# ShieldPotencia.net
KiCad netlist of a schematic drawn in EAGLE
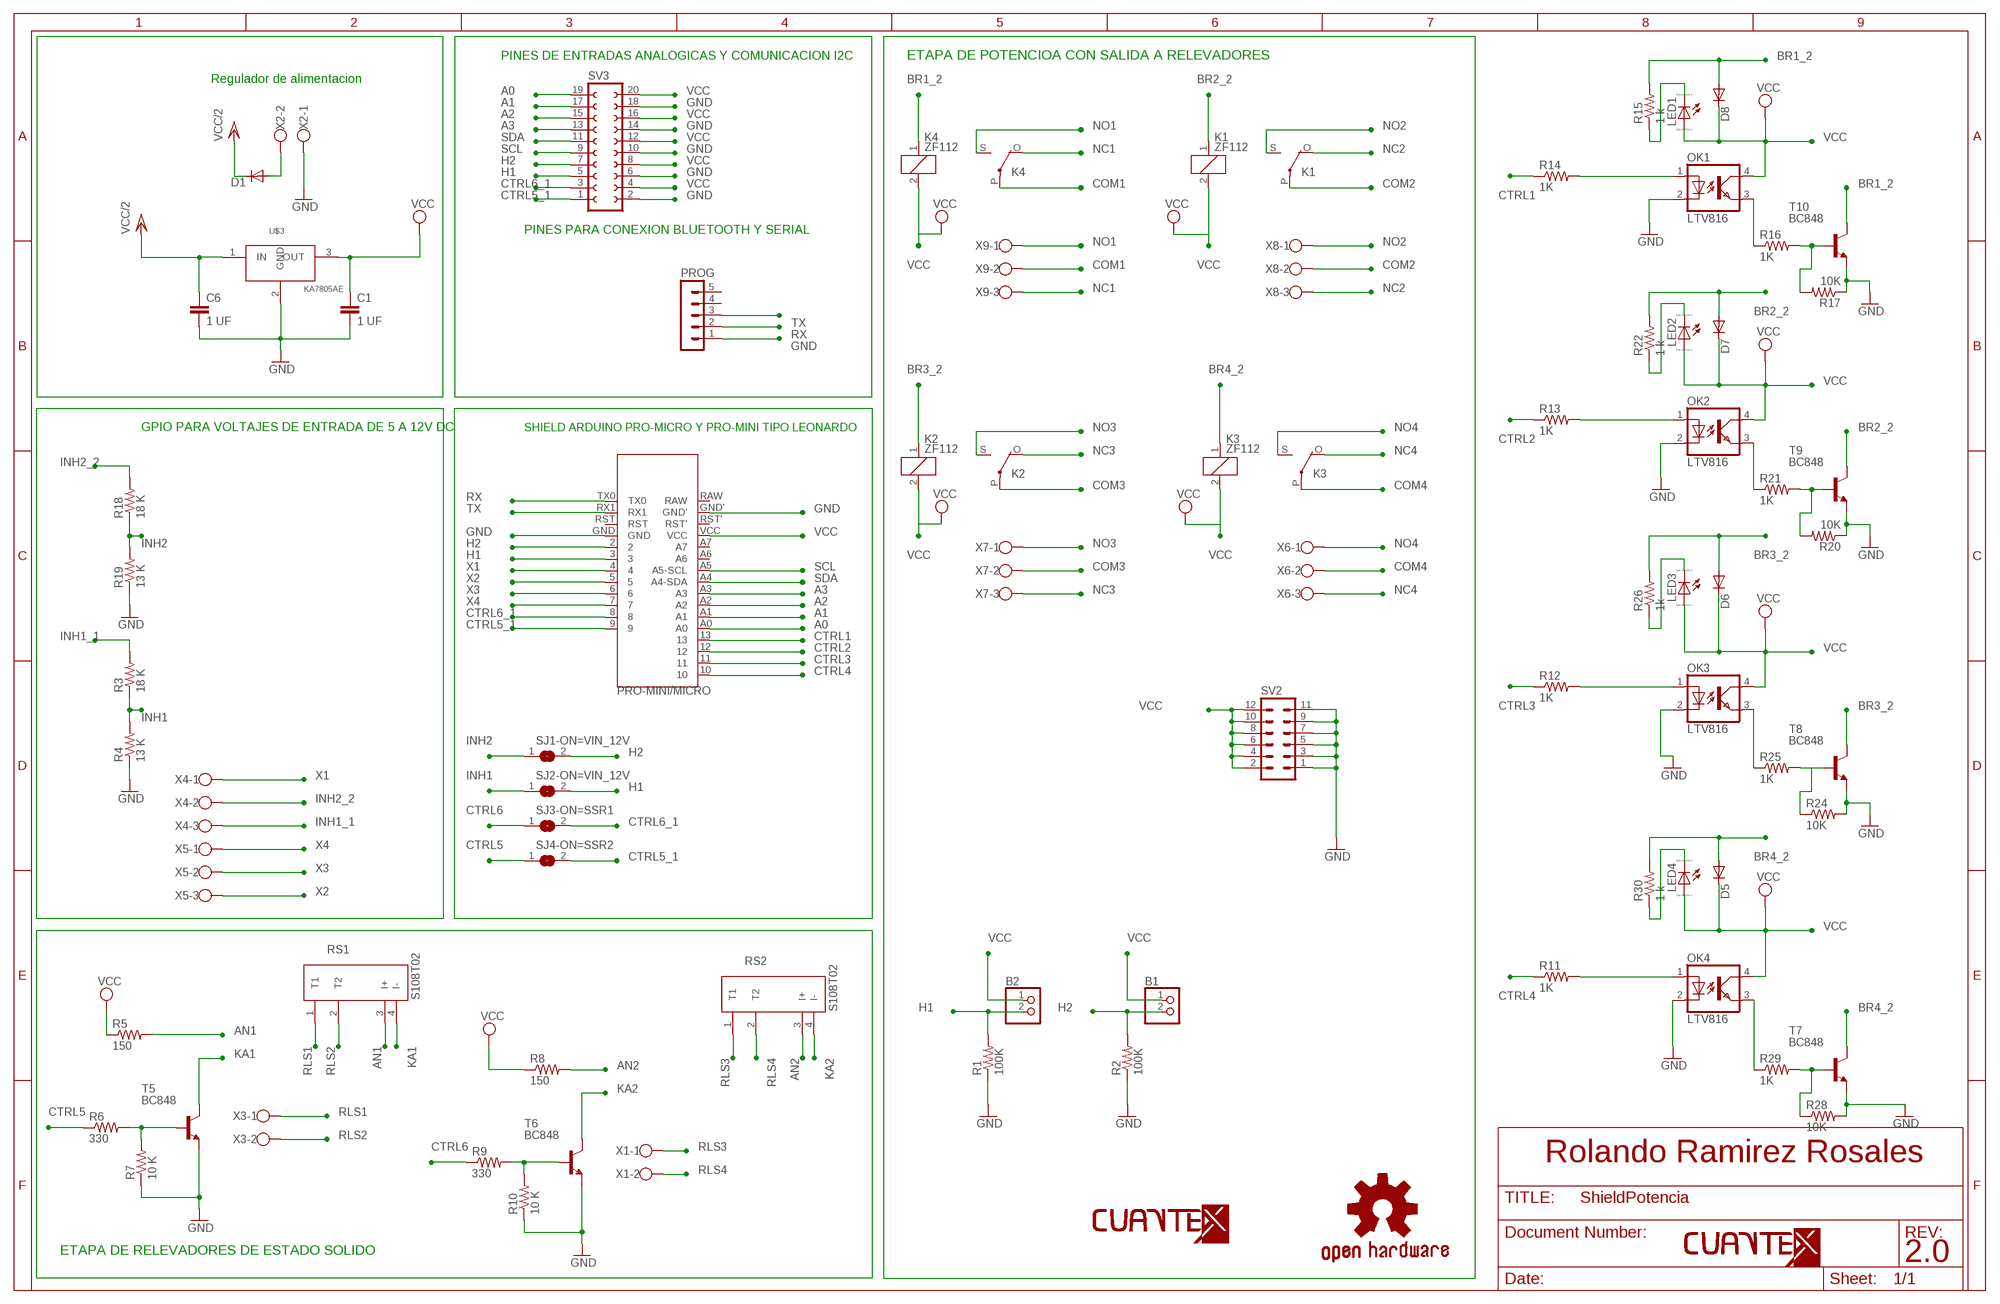
[diagram p0: schematic, sheet 1]

(export (version "E")
  (design (tool "Eeschema 10.0.6"))
  (components
    (comp (ref "B1")
      (value "PINHD-1X2")
      (footprint "eagle-import:1X02")
      (libsource (lib "eagle-import") (part "PINHD-1X2"))
    )
    (comp (ref "B2")
      (value "PINHD-1X2")
      (footprint "eagle-import:1X02")
      (libsource (lib "eagle-import") (part "PINHD-1X2"))
    )
    (comp (ref "C1")
      (value "1 UF")
      (footprint "eagle-import:C0603")
      (libsource (lib "eagle-import") (part "C-EUC0603"))
    )
    (comp (ref "C6")
      (value "1 UF")
      (footprint "eagle-import:C0603")
      (libsource (lib "eagle-import") (part "C-EUC0603"))
    )
    (comp (ref "D1")
      (value "DIODE-SMB")
      (footprint "eagle-import:SMB")
      (libsource (lib "eagle-import") (part "DIODE-SMB"))
    )
    (comp (ref "D5")
      (value "DIODE-SMB")
      (footprint "eagle-import:SMB")
      (libsource (lib "eagle-import") (part "DIODE-SMB"))
    )
    (comp (ref "D6")
      (value "DIODE-SMB")
      (footprint "eagle-import:SMB")
      (libsource (lib "eagle-import") (part "DIODE-SMB"))
    )
    (comp (ref "D7")
      (value "DIODE-SMB")
      (footprint "eagle-import:SMB")
      (libsource (lib "eagle-import") (part "DIODE-SMB"))
    )
    (comp (ref "D8")
      (value "DIODE-SMB")
      (footprint "eagle-import:SMB")
      (libsource (lib "eagle-import") (part "DIODE-SMB"))
    )
    (comp (ref "GOLD_ORB_SM1")
      (value "OSHWLOGO_GOLD_ORB_SM")
      (footprint "eagle-import:OSHW2")
      (libsource (lib "eagle-import") (part "OSHWLOGO_GOLD_ORB_SM"))
    )
    (comp (ref "K1")
      (value "ZF112")
      (footprint "eagle-import:ZF112")
      (libsource (lib "eagle-import") (part "ZF112"))
    )
    (comp (ref "K2")
      (value "ZF112")
      (footprint "eagle-import:ZF112")
      (libsource (lib "eagle-import") (part "ZF112"))
    )
    (comp (ref "K3")
      (value "ZF112")
      (footprint "eagle-import:ZF112")
      (libsource (lib "eagle-import") (part "ZF112"))
    )
    (comp (ref "K4")
      (value "ZF112")
      (footprint "eagle-import:ZF112")
      (libsource (lib "eagle-import") (part "ZF112"))
    )
    (comp (ref "LED1")
      (value "LED_ESML0603")
      (footprint "eagle-import:LED_SML0603")
      (libsource (lib "eagle-import") (part "LED_ESML0603"))
    )
    (comp (ref "LED2")
      (value "LED_ESML0603")
      (footprint "eagle-import:LED_SML0603")
      (libsource (lib "eagle-import") (part "LED_ESML0603"))
    )
    (comp (ref "LED3")
      (value "LED_ESML0603")
      (footprint "eagle-import:LED_SML0603")
      (libsource (lib "eagle-import") (part "LED_ESML0603"))
    )
    (comp (ref "LED4")
      (value "LED_ESML0603")
      (footprint "eagle-import:LED_SML0603")
      (libsource (lib "eagle-import") (part "LED_ESML0603"))
    )
    (comp (ref "OK1")
      (value "LTV816")
      (footprint "eagle-import:DIL04")
      (libsource (lib "eagle-import") (part "LTV816"))
    )
    (comp (ref "OK2")
      (value "LTV816")
      (footprint "eagle-import:DIL04")
      (libsource (lib "eagle-import") (part "LTV816"))
    )
    (comp (ref "OK3")
      (value "LTV816")
      (footprint "eagle-import:DIL04")
      (libsource (lib "eagle-import") (part "LTV816"))
    )
    (comp (ref "OK4")
      (value "LTV816")
      (footprint "eagle-import:DIL04")
      (libsource (lib "eagle-import") (part "LTV816"))
    )
    (comp (ref "PRO-MINI/MICRO")
      (value "ARDUINO_PRO_MINI_V1")
      (footprint "eagle-import:ARDUINO_PRO_MINI_V1")
      (libsource (lib "eagle-import") (part "ARDUINO_PRO_MINI_V1"))
    )
    (comp (ref "PROG")
      (value "MA05-1")
      (footprint "eagle-import:MA05-1")
      (libsource (lib "eagle-import") (part "MA05-1"))
    )
    (comp (ref "R1")
      (value "100K")
      (footprint "eagle-import:R0603")
      (libsource (lib "eagle-import") (part "R-US_R0603"))
    )
    (comp (ref "R2")
      (value "100K")
      (footprint "eagle-import:R0603")
      (libsource (lib "eagle-import") (part "R-US_R0603"))
    )
    (comp (ref "R3")
      (value "18 K")
      (footprint "eagle-import:R1206")
      (libsource (lib "eagle-import") (part "R-US_R1206"))
    )
    (comp (ref "R4")
      (value "13 K")
      (footprint "eagle-import:R1206")
      (libsource (lib "eagle-import") (part "R-US_R1206"))
    )
    (comp (ref "R5")
      (value "150")
      (footprint "eagle-import:R0603")
      (libsource (lib "eagle-import") (part "R-US_R0603"))
    )
    (comp (ref "R6")
      (value "330")
      (footprint "eagle-import:R0603")
      (libsource (lib "eagle-import") (part "R-US_R0603"))
    )
    (comp (ref "R7")
      (value "10 K")
      (footprint "eagle-import:R0603")
      (libsource (lib "eagle-import") (part "R-US_R0603"))
    )
    (comp (ref "R8")
      (value "150")
      (footprint "eagle-import:R0603")
      (libsource (lib "eagle-import") (part "R-US_R0603"))
    )
    (comp (ref "R9")
      (value "330")
      (footprint "eagle-import:R0603")
      (libsource (lib "eagle-import") (part "R-US_R0603"))
    )
    (comp (ref "R10")
      (value "10 K")
      (footprint "eagle-import:R0603")
      (libsource (lib "eagle-import") (part "R-US_R0603"))
    )
    (comp (ref "R11")
      (value "1K")
      (footprint "eagle-import:R0603")
      (libsource (lib "eagle-import") (part "R-US_R0603"))
    )
    (comp (ref "R12")
      (value "1K")
      (footprint "eagle-import:R0603")
      (libsource (lib "eagle-import") (part "R-US_R0603"))
    )
    (comp (ref "R13")
      (value "1K")
      (footprint "eagle-import:R0603")
      (libsource (lib "eagle-import") (part "R-US_R0603"))
    )
    (comp (ref "R14")
      (value "1K")
      (footprint "eagle-import:R0603")
      (libsource (lib "eagle-import") (part "R-US_R0603"))
    )
    (comp (ref "R15")
      (value "1 k")
      (footprint "eagle-import:R0603")
      (libsource (lib "eagle-import") (part "R-US_R0603"))
    )
    (comp (ref "R16")
      (value "1K")
      (footprint "eagle-import:R0603")
      (libsource (lib "eagle-import") (part "R-US_R0603"))
    )
    (comp (ref "R17")
      (value "10K")
      (footprint "eagle-import:R0603")
      (libsource (lib "eagle-import") (part "R-US_R0603"))
    )
    (comp (ref "R18")
      (value "18 K")
      (footprint "eagle-import:R1206")
      (libsource (lib "eagle-import") (part "R-US_R1206"))
    )
    (comp (ref "R19")
      (value "13 K")
      (footprint "eagle-import:R1206")
      (libsource (lib "eagle-import") (part "R-US_R1206"))
    )
    (comp (ref "R20")
      (value "10K")
      (footprint "eagle-import:R0603")
      (libsource (lib "eagle-import") (part "R-US_R0603"))
    )
    (comp (ref "R21")
      (value "1K")
      (footprint "eagle-import:R0603")
      (libsource (lib "eagle-import") (part "R-US_R0603"))
    )
    (comp (ref "R22")
      (value "1 k")
      (footprint "eagle-import:R0603")
      (libsource (lib "eagle-import") (part "R-US_R0603"))
    )
    (comp (ref "R24")
      (value "10K")
      (footprint "eagle-import:R0603")
      (libsource (lib "eagle-import") (part "R-US_R0603"))
    )
    (comp (ref "R25")
      (value "1K")
      (footprint "eagle-import:R0603")
      (libsource (lib "eagle-import") (part "R-US_R0603"))
    )
    (comp (ref "R26")
      (value "1k")
      (footprint "eagle-import:R0603")
      (libsource (lib "eagle-import") (part "R-US_R0603"))
    )
    (comp (ref "R28")
      (value "10K")
      (footprint "eagle-import:R0603")
      (libsource (lib "eagle-import") (part "R-US_R0603"))
    )
    (comp (ref "R29")
      (value "1K")
      (footprint "eagle-import:R0603")
      (libsource (lib "eagle-import") (part "R-US_R0603"))
    )
    (comp (ref "R30")
      (value "1 k")
      (footprint "eagle-import:R0603")
      (libsource (lib "eagle-import") (part "R-US_R0603"))
    )
    (comp (ref "RS1")
      (value "S108T02")
      (footprint "eagle-import:SIP4PIN")
      (libsource (lib "eagle-import") (part "S108T02"))
    )
    (comp (ref "RS2")
      (value "S108T02")
      (footprint "eagle-import:SIP4PIN")
      (libsource (lib "eagle-import") (part "S108T02"))
    )
    (comp (ref "SJ1-ON=VIN_12V")
      (value "SJ")
      (footprint "eagle-import:SJ")
      (libsource (lib "eagle-import") (part "SJ"))
    )
    (comp (ref "SJ2-ON=VIN_12V")
      (value "SJ")
      (footprint "eagle-import:SJ")
      (libsource (lib "eagle-import") (part "SJ"))
    )
    (comp (ref "SJ3-ON=SSR1")
      (value "SJ")
      (footprint "eagle-import:SJ")
      (libsource (lib "eagle-import") (part "SJ"))
    )
    (comp (ref "SJ4-ON=SSR2")
      (value "SJ")
      (footprint "eagle-import:SJ")
      (libsource (lib "eagle-import") (part "SJ"))
    )
    (comp (ref "SV2")
      (value "MA06-2")
      (footprint "eagle-import:MA06-2")
      (libsource (lib "eagle-import") (part "MA06-2"))
    )
    (comp (ref "SV3")
      (value "FE10-2")
      (footprint "eagle-import:FE10-2")
      (libsource (lib "eagle-import") (part "FE10-2"))
    )
    (comp (ref "T5")
      (value "BC848")
      (footprint "eagle-import:SOT23")
      (libsource (lib "eagle-import") (part "BC848"))
    )
    (comp (ref "T6")
      (value "BC848")
      (footprint "eagle-import:SOT23")
      (libsource (lib "eagle-import") (part "BC848"))
    )
    (comp (ref "T7")
      (value "BC848")
      (footprint "eagle-import:SOT23")
      (libsource (lib "eagle-import") (part "BC848"))
    )
    (comp (ref "T8")
      (value "BC848")
      (footprint "eagle-import:SOT23")
      (libsource (lib "eagle-import") (part "BC848"))
    )
    (comp (ref "T9")
      (value "BC848")
      (footprint "eagle-import:SOT23")
      (libsource (lib "eagle-import") (part "BC848"))
    )
    (comp (ref "T10")
      (value "BC848")
      (footprint "eagle-import:SOT23")
      (libsource (lib "eagle-import") (part "BC848"))
    )
    (comp (ref "U$1")
      (value "LOGO-TOP-50MM")
      (footprint "eagle-import:C-3")
      (libsource (lib "eagle-import") (part "LOGO-TOP-50MM"))
    )
    (comp (ref "U$2")
      (value "LOGO-TOP-20MM")
      (footprint "eagle-import:C-0")
      (libsource (lib "eagle-import") (part "LOGO-TOP-20MM"))
    )
    (comp (ref "U$3")
      (value "KA7805AE")
      (footprint "eagle-import:DPAK")
      (libsource (lib "eagle-import") (part "KA7805AE"))
    )
    (comp (ref "X1")
      (value "W237-102")
      (footprint "eagle-import:W237-102")
      (fields (field (name "MPN") "237-102"))
      (libsource (lib "eagle-import") (part "W237-102"))
    )
    (comp (ref "X2")
      (value "W237-102")
      (footprint "eagle-import:W237-102")
      (fields (field (name "MPN") "237-102"))
      (libsource (lib "eagle-import") (part "W237-102"))
    )
    (comp (ref "X3")
      (value "W237-102")
      (footprint "eagle-import:W237-102")
      (fields (field (name "MPN") "237-102"))
      (libsource (lib "eagle-import") (part "W237-102"))
    )
    (comp (ref "X4")
      (value "W237-103")
      (footprint "eagle-import:W237-103")
      (fields (field (name "MPN") "237-103"))
      (libsource (lib "eagle-import") (part "W237-103"))
    )
    (comp (ref "X5")
      (value "W237-103")
      (footprint "eagle-import:W237-103")
      (fields (field (name "MPN") "237-103"))
      (libsource (lib "eagle-import") (part "W237-103"))
    )
    (comp (ref "X6")
      (value "W237-103")
      (footprint "eagle-import:W237-103")
      (fields (field (name "MPN") "237-103"))
      (libsource (lib "eagle-import") (part "W237-103"))
    )
    (comp (ref "X7")
      (value "W237-103")
      (footprint "eagle-import:W237-103")
      (fields (field (name "MPN") "237-103"))
      (libsource (lib "eagle-import") (part "W237-103"))
    )
    (comp (ref "X8")
      (value "W237-103")
      (footprint "eagle-import:W237-103")
      (fields (field (name "MPN") "237-103"))
      (libsource (lib "eagle-import") (part "W237-103"))
    )
    (comp (ref "X9")
      (value "W237-103")
      (footprint "eagle-import:W237-103")
      (fields (field (name "MPN") "237-103"))
      (libsource (lib "eagle-import") (part "W237-103"))
    )
  )
  (nets
    (net (code "1") (name "/A0") (class "Default")
      (node (ref "PRO-MINI/MICRO") (pin "A0") (pinfunction "A0_A0") (pintype "bidirectional"))
      (node (ref "SV3") (pin "19") (pinfunction "19_19") (pintype "passive"))
    )
    (net (code "2") (name "/A1") (class "Default")
      (node (ref "PRO-MINI/MICRO") (pin "A1") (pinfunction "A1_A1") (pintype "bidirectional"))
      (node (ref "SV3") (pin "17") (pinfunction "17_17") (pintype "passive"))
    )
    (net (code "3") (name "/A2") (class "Default")
      (node (ref "PRO-MINI/MICRO") (pin "A2") (pinfunction "A2_A2") (pintype "bidirectional"))
      (node (ref "SV3") (pin "15") (pinfunction "15_15") (pintype "passive"))
    )
    (net (code "4") (name "/A3") (class "Default")
      (node (ref "PRO-MINI/MICRO") (pin "A3") (pinfunction "A3_A3") (pintype "bidirectional"))
      (node (ref "SV3") (pin "13") (pinfunction "13_13") (pintype "passive"))
    )
    (net (code "5") (name "/AN1") (class "Default")
      (node (ref "R5") (pin "2") (pinfunction "2_2") (pintype "passive"))
      (node (ref "RS1") (pin "3") (pinfunction "I+_3") (pintype "bidirectional"))
    )
    (net (code "6") (name "/AN2") (class "Default")
      (node (ref "R8") (pin "2") (pinfunction "2_2") (pintype "passive"))
      (node (ref "RS2") (pin "3") (pinfunction "I+_3") (pintype "bidirectional"))
    )
    (net (code "7") (name "/BR1_2") (class "Default")
      (node (ref "D8") (pin "A") (pinfunction "A_A") (pintype "passive"))
      (node (ref "K4") (pin "1") (pinfunction "1_1") (pintype "passive"))
      (node (ref "R15") (pin "2") (pinfunction "2_2") (pintype "passive"))
      (node (ref "T10") (pin "3") (pinfunction "C_3") (pintype "passive"))
    )
    (net (code "8") (name "/BR2_2") (class "Default")
      (node (ref "D7") (pin "A") (pinfunction "A_A") (pintype "passive"))
      (node (ref "K1") (pin "1") (pinfunction "1_1") (pintype "passive"))
      (node (ref "R22") (pin "2") (pinfunction "2_2") (pintype "passive"))
      (node (ref "T9") (pin "3") (pinfunction "C_3") (pintype "passive"))
    )
    (net (code "9") (name "/BR3_2") (class "Default")
      (node (ref "D6") (pin "A") (pinfunction "A_A") (pintype "passive"))
      (node (ref "K2") (pin "1") (pinfunction "1_1") (pintype "passive"))
      (node (ref "R26") (pin "2") (pinfunction "2_2") (pintype "passive"))
      (node (ref "T8") (pin "3") (pinfunction "C_3") (pintype "passive"))
    )
    (net (code "10") (name "/BR4_2") (class "Default")
      (node (ref "D5") (pin "A") (pinfunction "A_A") (pintype "passive"))
      (node (ref "K3") (pin "1") (pinfunction "1_1") (pintype "passive"))
      (node (ref "R30") (pin "2") (pinfunction "2_2") (pintype "passive"))
      (node (ref "T7") (pin "3") (pinfunction "C_3") (pintype "passive"))
    )
    (net (code "11") (name "/COM1") (class "Default")
      (node (ref "K4") (pin "P") (pinfunction "P_P") (pintype "passive"))
      (node (ref "X9") (pin "2") (pinfunction "KL_2") (pintype "passive"))
    )
    (net (code "12") (name "/COM2") (class "Default")
      (node (ref "K1") (pin "P") (pinfunction "P_P") (pintype "passive"))
      (node (ref "X8") (pin "2") (pinfunction "KL_2") (pintype "passive"))
    )
    (net (code "13") (name "/COM3") (class "Default")
      (node (ref "K2") (pin "P") (pinfunction "P_P") (pintype "passive"))
      (node (ref "X7") (pin "2") (pinfunction "KL_2") (pintype "passive"))
    )
    (net (code "14") (name "/COM4") (class "Default")
      (node (ref "K3") (pin "P") (pinfunction "P_P") (pintype "passive"))
      (node (ref "X6") (pin "2") (pinfunction "KL_2") (pintype "passive"))
    )
    (net (code "15") (name "/CTRL1") (class "Default")
      (node (ref "PRO-MINI/MICRO") (pin "13") (pinfunction "13_13") (pintype "bidirectional"))
      (node (ref "R14") (pin "1") (pinfunction "1_1") (pintype "passive"))
    )
    (net (code "16") (name "/CTRL2") (class "Default")
      (node (ref "PRO-MINI/MICRO") (pin "12") (pinfunction "12_12") (pintype "bidirectional"))
      (node (ref "R13") (pin "1") (pinfunction "1_1") (pintype "passive"))
    )
    (net (code "17") (name "/CTRL3") (class "Default")
      (node (ref "PRO-MINI/MICRO") (pin "11") (pinfunction "11_11") (pintype "bidirectional"))
      (node (ref "R12") (pin "1") (pinfunction "1_1") (pintype "passive"))
    )
    (net (code "18") (name "/CTRL4") (class "Default")
      (node (ref "PRO-MINI/MICRO") (pin "10") (pinfunction "10_10") (pintype "bidirectional"))
      (node (ref "R11") (pin "1") (pinfunction "1_1") (pintype "passive"))
    )
    (net (code "19") (name "/CTRL5") (class "Default")
      (node (ref "R6") (pin "1") (pinfunction "1_1") (pintype "passive"))
      (node (ref "SJ4-ON=SSR2") (pin "1") (pinfunction "1_1") (pintype "passive"))
    )
    (net (code "20") (name "/CTRL5_1") (class "Default")
      (node (ref "PRO-MINI/MICRO") (pin "9") (pinfunction "9_9") (pintype "bidirectional"))
      (node (ref "SJ4-ON=SSR2") (pin "2") (pinfunction "2_2") (pintype "passive"))
      (node (ref "SV3") (pin "1") (pinfunction "1_1") (pintype "passive"))
    )
    (net (code "21") (name "/CTRL6") (class "Default")
      (node (ref "R9") (pin "1") (pinfunction "1_1") (pintype "passive"))
      (node (ref "SJ3-ON=SSR1") (pin "1") (pinfunction "1_1") (pintype "passive"))
    )
    (net (code "22") (name "/CTRL6_1") (class "Default")
      (node (ref "PRO-MINI/MICRO") (pin "8") (pinfunction "8_8") (pintype "bidirectional"))
      (node (ref "SJ3-ON=SSR1") (pin "2") (pinfunction "2_2") (pintype "passive"))
      (node (ref "SV3") (pin "3") (pinfunction "3_3") (pintype "passive"))
    )
    (net (code "23") (name "/H1") (class "Default")
      (node (ref "B2") (pin "2") (pinfunction "2_2") (pintype "passive"))
      (node (ref "PRO-MINI/MICRO") (pin "3") (pinfunction "3_3") (pintype "bidirectional"))
      (node (ref "R1") (pin "2") (pinfunction "2_2") (pintype "passive"))
      (node (ref "SJ2-ON=VIN_12V") (pin "2") (pinfunction "2_2") (pintype "passive"))
      (node (ref "SV3") (pin "5") (pinfunction "5_5") (pintype "passive"))
    )
    (net (code "24") (name "/H2") (class "Default")
      (node (ref "B1") (pin "2") (pinfunction "2_2") (pintype "passive"))
      (node (ref "PRO-MINI/MICRO") (pin "2") (pinfunction "2_2") (pintype "bidirectional"))
      (node (ref "R2") (pin "2") (pinfunction "2_2") (pintype "passive"))
      (node (ref "SJ1-ON=VIN_12V") (pin "2") (pinfunction "2_2") (pintype "passive"))
      (node (ref "SV3") (pin "7") (pinfunction "7_7") (pintype "passive"))
    )
    (net (code "25") (name "/INH1") (class "Default")
      (node (ref "R3") (pin "1") (pinfunction "1_1") (pintype "passive"))
      (node (ref "R4") (pin "2") (pinfunction "2_2") (pintype "passive"))
      (node (ref "SJ2-ON=VIN_12V") (pin "1") (pinfunction "1_1") (pintype "passive"))
    )
    (net (code "26") (name "/INH1_1") (class "Default")
      (node (ref "R3") (pin "2") (pinfunction "2_2") (pintype "passive"))
      (node (ref "X4") (pin "3") (pinfunction "KL_3") (pintype "passive"))
    )
    (net (code "27") (name "/INH2") (class "Default")
      (node (ref "R18") (pin "1") (pinfunction "1_1") (pintype "passive"))
      (node (ref "R19") (pin "2") (pinfunction "2_2") (pintype "passive"))
      (node (ref "SJ1-ON=VIN_12V") (pin "1") (pinfunction "1_1") (pintype "passive"))
    )
    (net (code "28") (name "/INH2_2") (class "Default")
      (node (ref "R18") (pin "2") (pinfunction "2_2") (pintype "passive"))
      (node (ref "X4") (pin "2") (pinfunction "KL_2") (pintype "passive"))
    )
    (net (code "29") (name "/KA1") (class "Default")
      (node (ref "RS1") (pin "4") (pinfunction "I-_4") (pintype "bidirectional"))
      (node (ref "T5") (pin "3") (pinfunction "C_3") (pintype "passive"))
    )
    (net (code "30") (name "/KA2") (class "Default")
      (node (ref "RS2") (pin "4") (pinfunction "I-_4") (pintype "bidirectional"))
      (node (ref "T6") (pin "3") (pinfunction "C_3") (pintype "passive"))
    )
    (net (code "31") (name "/NC1") (class "Default")
      (node (ref "K4") (pin "O") (pinfunction "O_O") (pintype "passive"))
      (node (ref "X9") (pin "3") (pinfunction "KL_3") (pintype "passive"))
    )
    (net (code "32") (name "/NC2") (class "Default")
      (node (ref "K1") (pin "O") (pinfunction "O_O") (pintype "passive"))
      (node (ref "X8") (pin "3") (pinfunction "KL_3") (pintype "passive"))
    )
    (net (code "33") (name "/NC3") (class "Default")
      (node (ref "K2") (pin "O") (pinfunction "O_O") (pintype "passive"))
      (node (ref "X7") (pin "3") (pinfunction "KL_3") (pintype "passive"))
    )
    (net (code "34") (name "/NC4") (class "Default")
      (node (ref "K3") (pin "O") (pinfunction "O_O") (pintype "passive"))
      (node (ref "X6") (pin "3") (pinfunction "KL_3") (pintype "passive"))
    )
    (net (code "35") (name "/NO1") (class "Default")
      (node (ref "K4") (pin "S") (pinfunction "S_S") (pintype "passive"))
      (node (ref "X9") (pin "1") (pinfunction "KL_1") (pintype "passive"))
    )
    (net (code "36") (name "/NO2") (class "Default")
      (node (ref "K1") (pin "S") (pinfunction "S_S") (pintype "passive"))
      (node (ref "X8") (pin "1") (pinfunction "KL_1") (pintype "passive"))
    )
    (net (code "37") (name "/NO3") (class "Default")
      (node (ref "K2") (pin "S") (pinfunction "S_S") (pintype "passive"))
      (node (ref "X7") (pin "1") (pinfunction "KL_1") (pintype "passive"))
    )
    (net (code "38") (name "/NO4") (class "Default")
      (node (ref "K3") (pin "S") (pinfunction "S_S") (pintype "passive"))
      (node (ref "X6") (pin "1") (pinfunction "KL_1") (pintype "passive"))
    )
    (net (code "39") (name "/RLS1") (class "Default")
      (node (ref "RS1") (pin "1") (pinfunction "T1_1") (pintype "bidirectional"))
      (node (ref "X3") (pin "1") (pinfunction "KL_1") (pintype "passive"))
    )
    (net (code "40") (name "/RLS2") (class "Default")
      (node (ref "RS1") (pin "2") (pinfunction "T2_2") (pintype "bidirectional"))
      (node (ref "X3") (pin "2") (pinfunction "KL_2") (pintype "passive"))
    )
    (net (code "41") (name "/RLS3") (class "Default")
      (node (ref "RS2") (pin "1") (pinfunction "T1_1") (pintype "bidirectional"))
      (node (ref "X1") (pin "1") (pinfunction "KL_1") (pintype "passive"))
    )
    (net (code "42") (name "/RLS4") (class "Default")
      (node (ref "RS2") (pin "2") (pinfunction "T2_2") (pintype "bidirectional"))
      (node (ref "X1") (pin "2") (pinfunction "KL_2") (pintype "passive"))
    )
    (net (code "43") (name "/RX") (class "Default")
      (node (ref "PRO-MINI/MICRO") (pin "TX0") (pinfunction "TX0_TX0") (pintype "bidirectional"))
      (node (ref "PROG") (pin "2") (pinfunction "2_2") (pintype "passive"))
    )
    (net (code "44") (name "/SCL") (class "Default")
      (node (ref "PRO-MINI/MICRO") (pin "A5") (pinfunction "A5-SCL_A5") (pintype "bidirectional"))
      (node (ref "SV3") (pin "9") (pinfunction "9_9") (pintype "passive"))
    )
    (net (code "45") (name "/SDA") (class "Default")
      (node (ref "PRO-MINI/MICRO") (pin "A4") (pinfunction "A4-SDA_A4") (pintype "bidirectional"))
      (node (ref "SV3") (pin "11") (pinfunction "11_11") (pintype "passive"))
    )
    (net (code "46") (name "/TX") (class "Default")
      (node (ref "PRO-MINI/MICRO") (pin "RX1") (pinfunction "RX1_RX1") (pintype "bidirectional"))
      (node (ref "PROG") (pin "3") (pinfunction "3_3") (pintype "passive"))
    )
    (net (code "47") (name "/X1") (class "Default")
      (node (ref "PRO-MINI/MICRO") (pin "4") (pinfunction "4_4") (pintype "bidirectional"))
      (node (ref "X4") (pin "1") (pinfunction "KL_1") (pintype "passive"))
    )
    (net (code "48") (name "/X2") (class "Default")
      (node (ref "PRO-MINI/MICRO") (pin "5") (pinfunction "5_5") (pintype "bidirectional"))
      (node (ref "X5") (pin "3") (pinfunction "KL_3") (pintype "passive"))
    )
    (net (code "49") (name "/X3") (class "Default")
      (node (ref "PRO-MINI/MICRO") (pin "6") (pinfunction "6_6") (pintype "bidirectional"))
      (node (ref "X5") (pin "2") (pinfunction "KL_2") (pintype "passive"))
    )
    (net (code "50") (name "/X4") (class "Default")
      (node (ref "PRO-MINI/MICRO") (pin "7") (pinfunction "7_7") (pintype "bidirectional"))
      (node (ref "X5") (pin "1") (pinfunction "KL_1") (pintype "passive"))
    )
    (net (code "51") (name "GND") (class "Default")
      (node (ref "C1") (pin "2") (pinfunction "2_2") (pintype "passive"))
      (node (ref "C6") (pin "2") (pinfunction "2_2") (pintype "passive"))
      (node (ref "OK1") (pin "2") (pinfunction "C_2") (pintype "passive"))
      (node (ref "OK2") (pin "2") (pinfunction "C_2") (pintype "passive"))
      (node (ref "OK3") (pin "2") (pinfunction "C_2") (pintype "passive"))
      (node (ref "OK4") (pin "2") (pinfunction "C_2") (pintype "passive"))
      (node (ref "PRO-MINI/MICRO") (pin "GND") (pinfunction "GND_GND") (pintype "bidirectional"))
      (node (ref "PRO-MINI/MICRO") (pin "GND'") (pinfunction "GND'_GND'") (pintype "bidirectional"))
      (node (ref "PROG") (pin "1") (pinfunction "1_1") (pintype "passive"))
      (node (ref "R1") (pin "1") (pinfunction "1_1") (pintype "passive"))
      (node (ref "R10") (pin "1") (pinfunction "1_1") (pintype "passive"))
      (node (ref "R17") (pin "1") (pinfunction "1_1") (pintype "passive"))
      (node (ref "R19") (pin "1") (pinfunction "1_1") (pintype "passive"))
      (node (ref "R2") (pin "1") (pinfunction "1_1") (pintype "passive"))
      (node (ref "R20") (pin "1") (pinfunction "1_1") (pintype "passive"))
      (node (ref "R24") (pin "2") (pinfunction "2_2") (pintype "passive"))
      (node (ref "R28") (pin "2") (pinfunction "2_2") (pintype "passive"))
      (node (ref "R4") (pin "1") (pinfunction "1_1") (pintype "passive"))
      (node (ref "R7") (pin "1") (pinfunction "1_1") (pintype "passive"))
      (node (ref "SV2") (pin "1") (pinfunction "1_1") (pintype "passive"))
      (node (ref "SV2") (pin "11") (pinfunction "11_11") (pintype "passive"))
      (node (ref "SV2") (pin "3") (pinfunction "3_3") (pintype "passive"))
      (node (ref "SV2") (pin "5") (pinfunction "5_5") (pintype "passive"))
      (node (ref "SV2") (pin "7") (pinfunction "7_7") (pintype "passive"))
      (node (ref "SV2") (pin "9") (pinfunction "9_9") (pintype "passive"))
      (node (ref "SV3") (pin "10") (pinfunction "10_10") (pintype "passive"))
      (node (ref "SV3") (pin "14") (pinfunction "14_14") (pintype "passive"))
      (node (ref "SV3") (pin "18") (pinfunction "18_18") (pintype "passive"))
      (node (ref "SV3") (pin "2") (pinfunction "2_2") (pintype "passive"))
      (node (ref "SV3") (pin "6") (pinfunction "6_6") (pintype "passive"))
      (node (ref "T10") (pin "2") (pinfunction "E_2") (pintype "passive"))
      (node (ref "T5") (pin "2") (pinfunction "E_2") (pintype "passive"))
      (node (ref "T6") (pin "2") (pinfunction "E_2") (pintype "passive"))
      (node (ref "T7") (pin "2") (pinfunction "E_2") (pintype "passive"))
      (node (ref "T8") (pin "2") (pinfunction "E_2") (pintype "passive"))
      (node (ref "T9") (pin "2") (pinfunction "E_2") (pintype "passive"))
      (node (ref "U$3") (pin "2") (pinfunction "GND_2") (pintype "bidirectional"))
      (node (ref "X2") (pin "1") (pinfunction "KL_1") (pintype "passive"))
    )
    (net (code "52") (name "Net-(LED1-PadC)") (class "Default")
      (node (ref "LED1") (pin "C") (pinfunction "C_C") (pintype "passive"))
      (node (ref "R15") (pin "1") (pinfunction "1_1") (pintype "passive"))
    )
    (net (code "53") (name "Net-(LED2-PadC)") (class "Default")
      (node (ref "LED2") (pin "C") (pinfunction "C_C") (pintype "passive"))
      (node (ref "R22") (pin "1") (pinfunction "1_1") (pintype "passive"))
    )
    (net (code "54") (name "Net-(LED3-PadC)") (class "Default")
      (node (ref "LED3") (pin "C") (pinfunction "C_C") (pintype "passive"))
      (node (ref "R26") (pin "1") (pinfunction "1_1") (pintype "passive"))
    )
    (net (code "55") (name "Net-(LED4-PadC)") (class "Default")
      (node (ref "LED4") (pin "C") (pinfunction "C_C") (pintype "passive"))
      (node (ref "R30") (pin "1") (pinfunction "1_1") (pintype "passive"))
    )
    (net (code "56") (name "Net-(OK1-A)") (class "Default")
      (node (ref "OK1") (pin "1") (pinfunction "A_1") (pintype "passive"))
      (node (ref "R14") (pin "2") (pinfunction "2_2") (pintype "passive"))
    )
    (net (code "57") (name "Net-(OK1-EMIT)") (class "Default")
      (node (ref "OK1") (pin "3") (pinfunction "EMIT_3") (pintype "passive"))
      (node (ref "R16") (pin "1") (pinfunction "1_1") (pintype "passive"))
    )
    (net (code "58") (name "Net-(OK2-A)") (class "Default")
      (node (ref "OK2") (pin "1") (pinfunction "A_1") (pintype "passive"))
      (node (ref "R13") (pin "2") (pinfunction "2_2") (pintype "passive"))
    )
    (net (code "59") (name "Net-(OK2-EMIT)") (class "Default")
      (node (ref "OK2") (pin "3") (pinfunction "EMIT_3") (pintype "passive"))
      (node (ref "R21") (pin "1") (pinfunction "1_1") (pintype "passive"))
    )
    (net (code "60") (name "Net-(OK3-A)") (class "Default")
      (node (ref "OK3") (pin "1") (pinfunction "A_1") (pintype "passive"))
      (node (ref "R12") (pin "2") (pinfunction "2_2") (pintype "passive"))
    )
    (net (code "61") (name "Net-(OK3-EMIT)") (class "Default")
      (node (ref "OK3") (pin "3") (pinfunction "EMIT_3") (pintype "passive"))
      (node (ref "R25") (pin "1") (pinfunction "1_1") (pintype "passive"))
    )
    (net (code "62") (name "Net-(OK4-A)") (class "Default")
      (node (ref "OK4") (pin "1") (pinfunction "A_1") (pintype "passive"))
      (node (ref "R11") (pin "2") (pinfunction "2_2") (pintype "passive"))
    )
    (net (code "63") (name "Net-(OK4-EMIT)") (class "Default")
      (node (ref "OK4") (pin "3") (pinfunction "EMIT_3") (pintype "passive"))
      (node (ref "R29") (pin "1") (pinfunction "1_1") (pintype "passive"))
    )
    (net (code "64") (name "Net-(T5-B)") (class "Default")
      (node (ref "R6") (pin "2") (pinfunction "2_2") (pintype "passive"))
      (node (ref "R7") (pin "2") (pinfunction "2_2") (pintype "passive"))
      (node (ref "T5") (pin "1") (pinfunction "B_1") (pintype "passive"))
    )
    (net (code "65") (name "Net-(T6-B)") (class "Default")
      (node (ref "R10") (pin "2") (pinfunction "2_2") (pintype "passive"))
      (node (ref "R9") (pin "2") (pinfunction "2_2") (pintype "passive"))
      (node (ref "T6") (pin "1") (pinfunction "B_1") (pintype "passive"))
    )
    (net (code "66") (name "Net-(T7-B)") (class "Default")
      (node (ref "R28") (pin "1") (pinfunction "1_1") (pintype "passive"))
      (node (ref "R29") (pin "2") (pinfunction "2_2") (pintype "passive"))
      (node (ref "T7") (pin "1") (pinfunction "B_1") (pintype "passive"))
    )
    (net (code "67") (name "Net-(T8-B)") (class "Default")
      (node (ref "R24") (pin "1") (pinfunction "1_1") (pintype "passive"))
      (node (ref "R25") (pin "2") (pinfunction "2_2") (pintype "passive"))
      (node (ref "T8") (pin "1") (pinfunction "B_1") (pintype "passive"))
    )
    (net (code "68") (name "Net-(T9-B)") (class "Default")
      (node (ref "R20") (pin "2") (pinfunction "2_2") (pintype "passive"))
      (node (ref "R21") (pin "2") (pinfunction "2_2") (pintype "passive"))
      (node (ref "T9") (pin "1") (pinfunction "B_1") (pintype "passive"))
    )
    (net (code "69") (name "Net-(T10-B)") (class "Default")
      (node (ref "R16") (pin "2") (pinfunction "2_2") (pintype "passive"))
      (node (ref "R17") (pin "2") (pinfunction "2_2") (pintype "passive"))
      (node (ref "T10") (pin "1") (pinfunction "B_1") (pintype "passive"))
    )
    (net (code "70") (name "Net-(X2B-KL)") (class "Default")
      (node (ref "D1") (pin "A") (pinfunction "A_A") (pintype "passive"))
      (node (ref "X2") (pin "2") (pinfunction "KL_2") (pintype "passive"))
    )
    (net (code "71") (name "VCC") (class "Default")
      (node (ref "B1") (pin "1") (pinfunction "1_1") (pintype "passive"))
      (node (ref "B2") (pin "1") (pinfunction "1_1") (pintype "passive"))
      (node (ref "C1") (pin "1") (pinfunction "1_1") (pintype "passive"))
      (node (ref "D5") (pin "C") (pinfunction "C_C") (pintype "passive"))
      (node (ref "D6") (pin "C") (pinfunction "C_C") (pintype "passive"))
      (node (ref "D7") (pin "C") (pinfunction "C_C") (pintype "passive"))
      (node (ref "D8") (pin "C") (pinfunction "C_C") (pintype "passive"))
      (node (ref "K1") (pin "2") (pinfunction "2_2") (pintype "passive"))
      (node (ref "K2") (pin "2") (pinfunction "2_2") (pintype "passive"))
      (node (ref "K3") (pin "2") (pinfunction "2_2") (pintype "passive"))
      (node (ref "K4") (pin "2") (pinfunction "2_2") (pintype "passive"))
      (node (ref "LED1") (pin "A") (pinfunction "A_A") (pintype "passive"))
      (node (ref "LED2") (pin "A") (pinfunction "A_A") (pintype "passive"))
      (node (ref "LED3") (pin "A") (pinfunction "A_A") (pintype "passive"))
      (node (ref "LED4") (pin "A") (pinfunction "A_A") (pintype "passive"))
      (node (ref "OK1") (pin "4") (pinfunction "COL_4") (pintype "passive"))
      (node (ref "OK2") (pin "4") (pinfunction "COL_4") (pintype "passive"))
      (node (ref "OK3") (pin "4") (pinfunction "COL_4") (pintype "passive"))
      (node (ref "OK4") (pin "4") (pinfunction "COL_4") (pintype "passive"))
      (node (ref "PRO-MINI/MICRO") (pin "VCC") (pinfunction "VCC_VCC") (pintype "bidirectional"))
      (node (ref "R5") (pin "1") (pinfunction "1_1") (pintype "passive"))
      (node (ref "R8") (pin "1") (pinfunction "1_1") (pintype "passive"))
      (node (ref "SV2") (pin "10") (pinfunction "10_10") (pintype "passive"))
      (node (ref "SV2") (pin "12") (pinfunction "12_12") (pintype "passive"))
      (node (ref "SV2") (pin "2") (pinfunction "2_2") (pintype "passive"))
      (node (ref "SV2") (pin "4") (pinfunction "4_4") (pintype "passive"))
      (node (ref "SV2") (pin "6") (pinfunction "6_6") (pintype "passive"))
      (node (ref "SV2") (pin "8") (pinfunction "8_8") (pintype "passive"))
      (node (ref "SV3") (pin "12") (pinfunction "12_12") (pintype "passive"))
      (node (ref "SV3") (pin "16") (pinfunction "16_16") (pintype "passive"))
      (node (ref "SV3") (pin "20") (pinfunction "20_20") (pintype "passive"))
      (node (ref "SV3") (pin "4") (pinfunction "4_4") (pintype "passive"))
      (node (ref "SV3") (pin "8") (pinfunction "8_8") (pintype "passive"))
      (node (ref "U$3") (pin "3") (pinfunction "OUT_3") (pintype "bidirectional"))
    )
    (net (code "72") (name "VCC{slash}2") (class "Default")
      (node (ref "C6") (pin "1") (pinfunction "1_1") (pintype "passive"))
      (node (ref "D1") (pin "C") (pinfunction "C_C") (pintype "passive"))
      (node (ref "U$3") (pin "1") (pinfunction "IN_1") (pintype "bidirectional"))
    )
    (net (code "73") (name "unconnected-(PRO-MINI/MICRO-PadA6)") (class "Default")
      (node (ref "PRO-MINI/MICRO") (pin "A6") (pinfunction "A6_A6") (pintype "bidirectional"))
    )
    (net (code "74") (name "unconnected-(PRO-MINI/MICRO-PadA7)") (class "Default")
      (node (ref "PRO-MINI/MICRO") (pin "A7") (pinfunction "A7_A7") (pintype "bidirectional"))
    )
    (net (code "75") (name "unconnected-(PRO-MINI/MICRO-PadRAW)") (class "Default")
      (node (ref "PRO-MINI/MICRO") (pin "RAW") (pinfunction "RAW_RAW") (pintype "bidirectional"))
    )
    (net (code "76") (name "unconnected-(PRO-MINI/MICRO-PadRST')") (class "Default")
      (node (ref "PRO-MINI/MICRO") (pin "RST'") (pinfunction "RST'_RST'") (pintype "bidirectional"))
    )
    (net (code "77") (name "unconnected-(PRO-MINI/MICRO-PadRST)") (class "Default")
      (node (ref "PRO-MINI/MICRO") (pin "RST") (pinfunction "RST_RST") (pintype "bidirectional"))
    )
    (net (code "78") (name "unconnected-(PROG-Pad4)") (class "Default")
      (node (ref "PROG") (pin "4") (pinfunction "4_4") (pintype "passive"))
    )
    (net (code "79") (name "unconnected-(PROG-Pad5)") (class "Default")
      (node (ref "PROG") (pin "5") (pinfunction "5_5") (pintype "passive"))
    )
  )
)
